# UHF_RFID_Nano_Shield.net
KiCad netlist of a schematic drawn in EAGLE
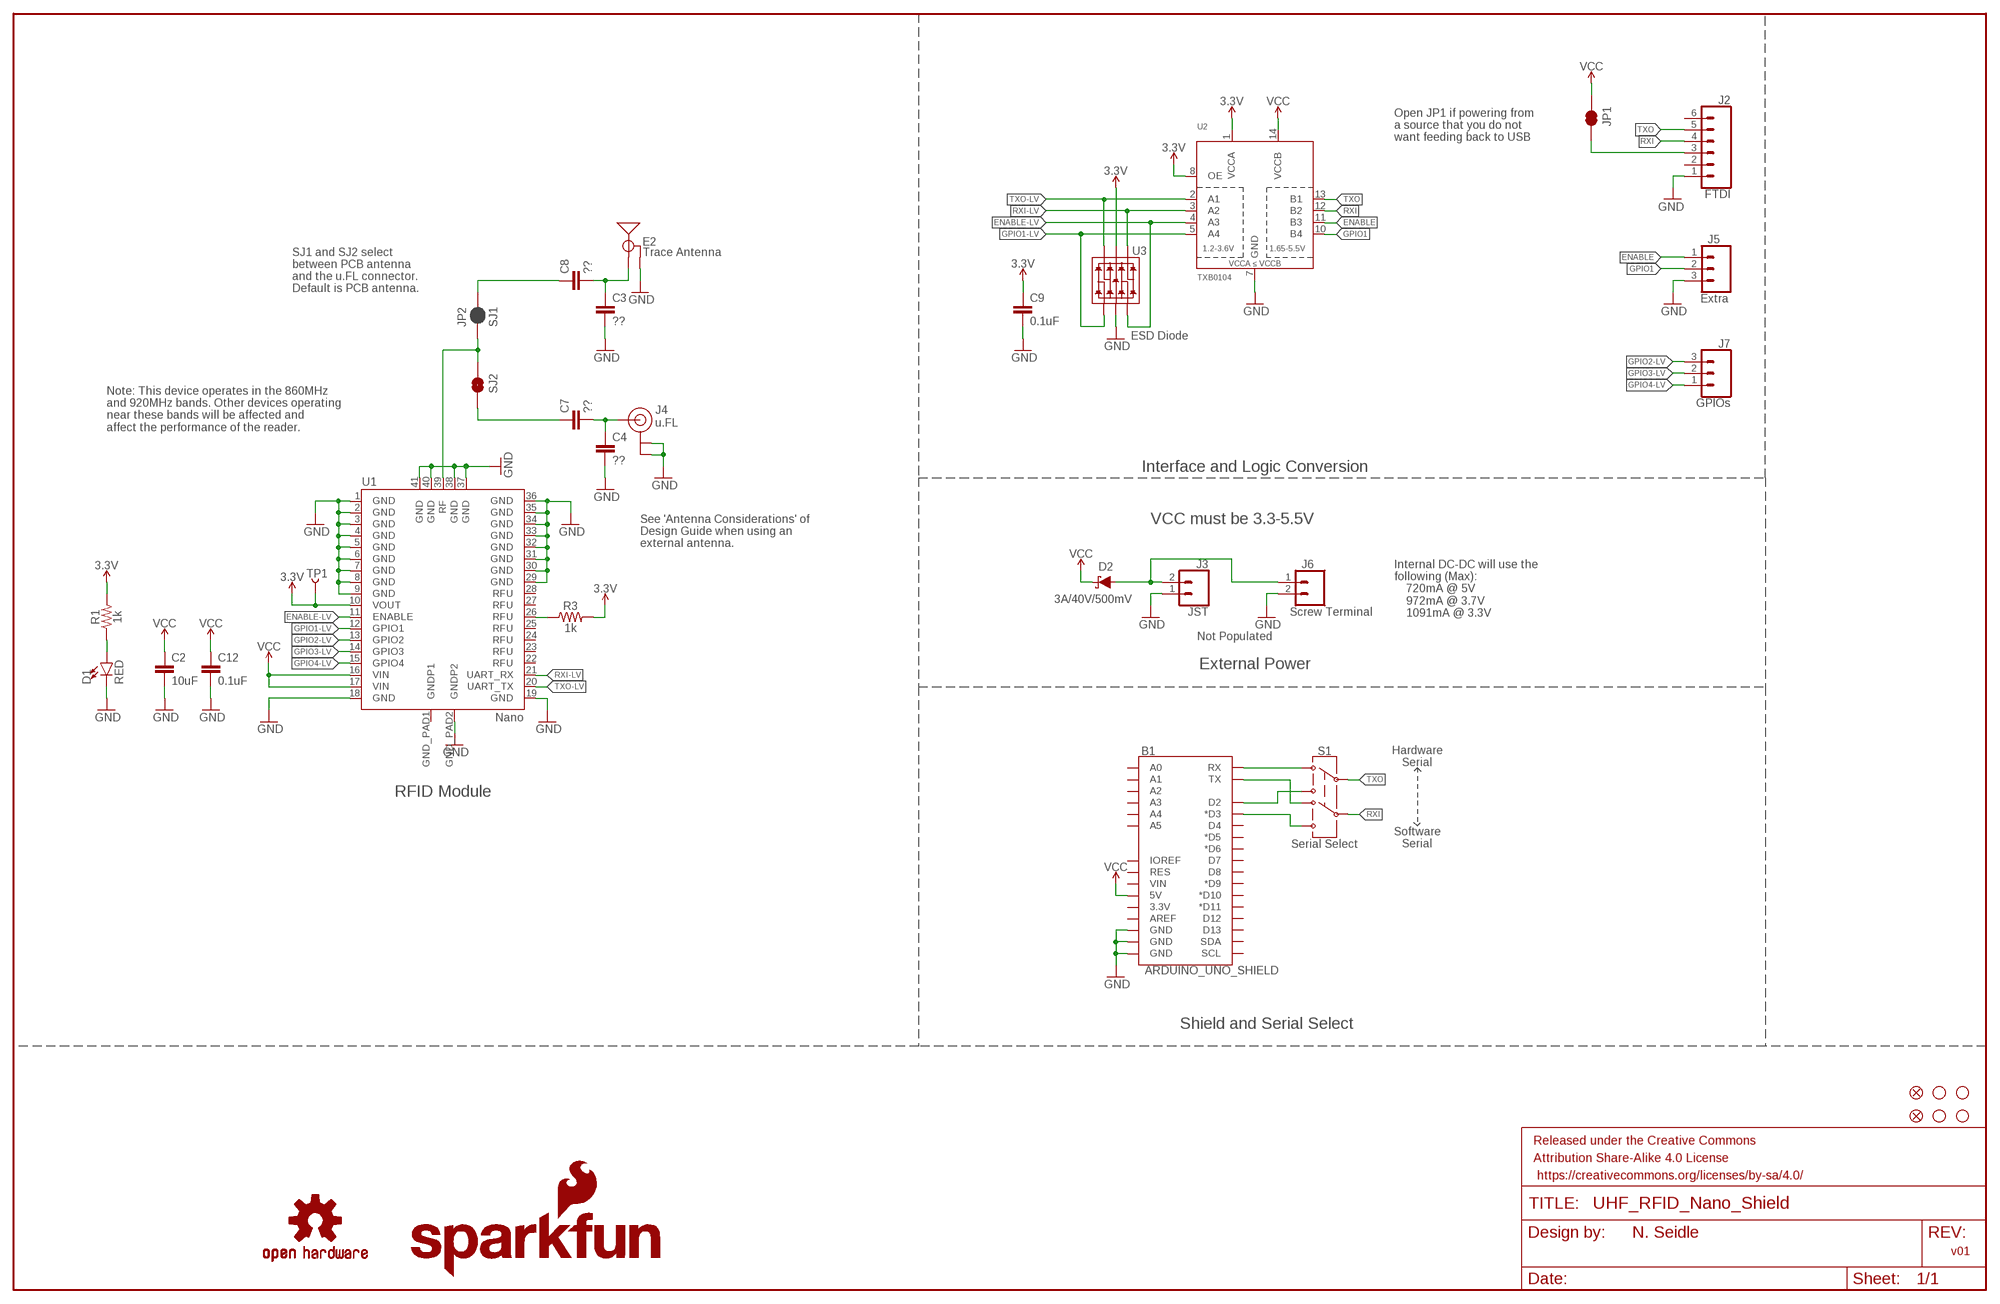
[diagram p0: schematic, sheet 1]

(export (version "E")
  (design (tool "Eeschema 10.0.6"))
  (components
    (comp (ref "B1")
      (value "ARDUINO_UNO_SHIELD")
      (footprint "eagle-import:UNO_R3_SHIELD")
      (libsource (lib "eagle-import") (part "ARDUINO_UNO_R3_SHIELDBASIC"))
    )
    (comp (ref "C2")
      (value "10uF")
      (footprint "eagle-import:0805")
      (libsource (lib "eagle-import") (part "10UF-0805-10V-10%"))
    )
    (comp (ref "C3")
      (value "??")
      (footprint "eagle-import:0603")
      (libsource (lib "eagle-import") (part "1.0PF-0603-50V-25%"))
    )
    (comp (ref "C4")
      (value "??")
      (footprint "eagle-import:0603")
      (libsource (lib "eagle-import") (part "1.0PF-0603-50V-25%"))
    )
    (comp (ref "C7")
      (value "??")
      (footprint "eagle-import:0603")
      (libsource (lib "eagle-import") (part "1.0PF-0603-50V-25%"))
    )
    (comp (ref "C8")
      (value "??")
      (footprint "eagle-import:0603")
      (libsource (lib "eagle-import") (part "1.0PF-0603-50V-25%"))
    )
    (comp (ref "C9")
      (value "0.1uF")
      (footprint "eagle-import:0603")
      (libsource (lib "eagle-import") (part "0.1UF-0603-25V-(+80/-20%)"))
    )
    (comp (ref "C12")
      (value "0.1uF")
      (footprint "eagle-import:0603")
      (libsource (lib "eagle-import") (part "0.1UF-0603-25V-(+80/-20%)"))
    )
    (comp (ref "D1")
      (value "RED")
      (footprint "eagle-import:LED-0603")
      (libsource (lib "eagle-import") (part "LED-RED0603"))
    )
    (comp (ref "D2")
      (value "3A/40V/500mV")
      (footprint "eagle-import:SMA-DIODE")
      (libsource (lib "eagle-import") (part "DIODE-SCHOTTKY-B340A"))
    )
    (comp (ref "E2")
      (value "Trace Antenna")
      (footprint "eagle-import:915MHZ_ANTENNA_TRIMBLE")
      (libsource (lib "eagle-import") (part "ANTENNA_GROUNDED1"))
    )
    (comp (ref "FID1")
      (value "FIDUCIAL1X2")
      (footprint "eagle-import:FIDUCIAL-1X2")
      (libsource (lib "eagle-import") (part "FIDUCIAL1X2"))
    )
    (comp (ref "FID2")
      (value "FIDUCIAL1X2")
      (footprint "eagle-import:FIDUCIAL-1X2")
      (libsource (lib "eagle-import") (part "FIDUCIAL1X2"))
    )
    (comp (ref "FRAME1")
      (value "FRAME-LEDGER")
      (footprint "eagle-import:CREATIVE_COMMONS")
      (libsource (lib "eagle-import") (part "FRAME-LEDGER"))
    )
    (comp (ref "J2")
      (value "FTDI")
      (footprint "eagle-import:1X06")
      (libsource (lib "eagle-import") (part "CONN_06SILK_FEMALE_PTH"))
    )
    (comp (ref "J3")
      (value "JST")
      (footprint "eagle-import:JST-2-PTH")
      (libsource (lib "eagle-import") (part "CONN_02JST-PTH-2"))
    )
    (comp (ref "J4")
      (value "U.FL")
      (footprint "eagle-import:U.FL")
      (libsource (lib "eagle-import") (part "U.FL"))
    )
    (comp (ref "J5")
      (value "Extra")
      (footprint "eagle-import:1X03")
      (libsource (lib "eagle-import") (part "CONN_03"))
    )
    (comp (ref "J6")
      (value "Screw Terminal")
      (footprint "eagle-import:SCREWTERMINAL-3.5MM-2")
      (libsource (lib "eagle-import") (part "CONN_023.5MM"))
    )
    (comp (ref "J7")
      (value "GPIOs")
      (footprint "eagle-import:1X03")
      (libsource (lib "eagle-import") (part "CONN_03"))
    )
    (comp (ref "JP1")
      (value "JUMPER-SMT_2_NC_TRACE_SILK")
      (footprint "eagle-import:SMT-JUMPER_2_NC_TRACE_SILK")
      (libsource (lib "eagle-import") (part "JUMPER-SMT_2_NC_TRACE_SILK"))
    )
    (comp (ref "JP2")
      (value "SJ1")
      (footprint "eagle-import:SMT-JUMPER_2_NO_NO-SILK")
      (libsource (lib "eagle-import") (part "JUMPER-SMT_2_NO_NO-SILK"))
    )
    (comp (ref "LOGO1")
      (value "SFE_LOGO_NAME_FLAME.1_INCH")
      (footprint "eagle-import:SFE_LOGO_NAME_FLAME_.1")
      (libsource (lib "eagle-import") (part "SFE_LOGO_NAME_FLAME.1_INCH"))
    )
    (comp (ref "LOGO2")
      (value "OSHW-LOGOS")
      (footprint "eagle-import:OSHW-LOGO-S")
      (libsource (lib "eagle-import") (part "OSHW-LOGOS"))
    )
    (comp (ref "LOGO3")
      (value "SFE_LOGO_NAME_FLAME.1_INCH")
      (footprint "eagle-import:SFE_LOGO_NAME_FLAME_.1")
      (libsource (lib "eagle-import") (part "SFE_LOGO_NAME_FLAME.1_INCH"))
    )
    (comp (ref "R1")
      (value "1k")
      (footprint "eagle-import:0603")
      (libsource (lib "eagle-import") (part "1KOHM-0603-1/10W-1%"))
    )
    (comp (ref "R3")
      (value "1k")
      (footprint "eagle-import:0603")
      (libsource (lib "eagle-import") (part "1KOHM-0603-1/10W-1%"))
    )
    (comp (ref "S1")
      (value "Serial Select")
      (footprint "eagle-import:SWITCH_DPDT_SMD_AYZ0202")
      (libsource (lib "eagle-import") (part "SWITCH-DPDT-SMD-AYZ0202"))
    )
    (comp (ref "SJ2")
      (value "JUMPER-SMT_2_NO_NO-SILK")
      (footprint "eagle-import:SMT-JUMPER_2_NO_NO-SILK")
      (libsource (lib "eagle-import") (part "JUMPER-SMT_2_NO_NO-SILK"))
    )
    (comp (ref "STANDOFF1")
      (value "STAND-OFF")
      (footprint "eagle-import:STAND-OFF")
      (libsource (lib "eagle-import") (part "STAND-OFF"))
    )
    (comp (ref "STANDOFF2")
      (value "STAND-OFF")
      (footprint "eagle-import:STAND-OFF")
      (libsource (lib "eagle-import") (part "STAND-OFF"))
    )
    (comp (ref "STANDOFF3")
      (value "STAND-OFF")
      (footprint "eagle-import:STAND-OFF")
      (libsource (lib "eagle-import") (part "STAND-OFF"))
    )
    (comp (ref "STANDOFF4")
      (value "STAND-OFF")
      (footprint "eagle-import:STAND-OFF")
      (libsource (lib "eagle-import") (part "STAND-OFF"))
    )
    (comp (ref "TP1")
      (value "TEST-POINT3")
      (footprint "eagle-import:PAD.03X.03")
      (libsource (lib "eagle-import") (part "TEST-POINT3"))
    )
    (comp (ref "U1")
      (value "Nano")
      (footprint "eagle-import:NANO_MODULE")
      (libsource (lib "eagle-import") (part "UHF_RFID_NANO_MODULE"))
    )
    (comp (ref "U2")
      (value "TXB0104")
      (footprint "eagle-import:SO14")
      (libsource (lib "eagle-import") (part "TXB0104PWRSOIC14"))
    )
    (comp (ref "U3")
      (value "ESD Diode")
      (footprint "eagle-import:SOT-23-6")
      (libsource (lib "eagle-import") (part "TVS_DIODE_ARRAYSMD"))
    )
  )
  (nets
    (net (code "1") (name "3.3V") (class "Default")
      (node (ref "C9") (pin "1") (pinfunction "1_1") (pintype "passive"))
      (node (ref "R1") (pin "2") (pinfunction "2_2") (pintype "passive"))
      (node (ref "R3") (pin "2") (pinfunction "2_2") (pintype "passive"))
      (node (ref "TP1") (pin "P$1") (pinfunction "1_P$1") (pintype "bidirectional"))
      (node (ref "U1") (pin "10") (pinfunction "VOUT_10") (pintype "bidirectional"))
      (node (ref "U2") (pin "1") (pinfunction "VCCA_1") (pintype "bidirectional"))
      (node (ref "U2") (pin "8") (pinfunction "OE_8") (pintype "bidirectional"))
      (node (ref "U3") (pin "5") (pinfunction "VCC_5") (pintype "bidirectional"))
    )
    (net (code "2") (name "ENABLE") (class "Default")
      (node (ref "J5") (pin "1") (pinfunction "1_1") (pintype "passive"))
      (node (ref "U2") (pin "11") (pinfunction "B3_11") (pintype "bidirectional"))
    )
    (net (code "3") (name "ENABLE-LV") (class "Default")
      (node (ref "U1") (pin "11") (pinfunction "ENABLE_11") (pintype "bidirectional"))
      (node (ref "U2") (pin "4") (pinfunction "A3_4") (pintype "bidirectional"))
      (node (ref "U3") (pin "3") (pinfunction "IO2_3") (pintype "bidirectional"))
    )
    (net (code "4") (name "GND") (class "Default")
      (node (ref "B1") (pin "GND@0") (pinfunction "GND_GND@0") (pintype "bidirectional"))
      (node (ref "B1") (pin "GND@1") (pinfunction "GND_GND@1") (pintype "bidirectional"))
      (node (ref "B1") (pin "GND@2") (pinfunction "GND_GND@2") (pintype "bidirectional"))
      (node (ref "C12") (pin "2") (pinfunction "2_2") (pintype "passive"))
      (node (ref "C2") (pin "2") (pinfunction "2_2") (pintype "passive"))
      (node (ref "C3") (pin "2") (pinfunction "2_2") (pintype "passive"))
      (node (ref "C4") (pin "2") (pinfunction "2_2") (pintype "passive"))
      (node (ref "C9") (pin "2") (pinfunction "2_2") (pintype "passive"))
      (node (ref "D1") (pin "C") (pinfunction "C_C") (pintype "passive"))
      (node (ref "E2") (pin "GND@1") (pinfunction "GND_GND@1") (pintype "bidirectional"))
      (node (ref "E2") (pin "GND@2") (pinfunction "GND_GND@2") (pintype "bidirectional"))
      (node (ref "E2") (pin "GND@3") (pinfunction "GND_GND@3") (pintype "bidirectional"))
      (node (ref "J2") (pin "1") (pinfunction "1_1") (pintype "passive"))
      (node (ref "J3") (pin "1") (pinfunction "1_1") (pintype "passive"))
      (node (ref "J4") (pin "P$1") (pinfunction "GND_P$1") (pintype "bidirectional"))
      (node (ref "J4") (pin "P$2") (pinfunction "GND_P$2") (pintype "bidirectional"))
      (node (ref "J5") (pin "3") (pinfunction "3_3") (pintype "passive"))
      (node (ref "J6") (pin "2") (pinfunction "2_2") (pintype "passive"))
      (node (ref "U1") (pin "1") (pinfunction "GND_1") (pintype "bidirectional"))
      (node (ref "U1") (pin "18") (pinfunction "GND_18") (pintype "bidirectional"))
      (node (ref "U1") (pin "19") (pinfunction "GND_19") (pintype "bidirectional"))
      (node (ref "U1") (pin "2") (pinfunction "GND_2") (pintype "bidirectional"))
      (node (ref "U1") (pin "29") (pinfunction "GND_29") (pintype "bidirectional"))
      (node (ref "U1") (pin "3") (pinfunction "GND_3") (pintype "bidirectional"))
      (node (ref "U1") (pin "30") (pinfunction "GND_30") (pintype "bidirectional"))
      (node (ref "U1") (pin "31") (pinfunction "GND_31") (pintype "bidirectional"))
      (node (ref "U1") (pin "32") (pinfunction "GND_32") (pintype "bidirectional"))
      (node (ref "U1") (pin "33") (pinfunction "GND_33") (pintype "bidirectional"))
      (node (ref "U1") (pin "34") (pinfunction "GND_34") (pintype "bidirectional"))
      (node (ref "U1") (pin "35") (pinfunction "GND_35") (pintype "bidirectional"))
      (node (ref "U1") (pin "36") (pinfunction "GND_36") (pintype "bidirectional"))
      (node (ref "U1") (pin "37") (pinfunction "GND_37") (pintype "bidirectional"))
      (node (ref "U1") (pin "38") (pinfunction "GND_38") (pintype "bidirectional"))
      (node (ref "U1") (pin "4") (pinfunction "GND_4") (pintype "bidirectional"))
      (node (ref "U1") (pin "40") (pinfunction "GND_40") (pintype "bidirectional"))
      (node (ref "U1") (pin "41") (pinfunction "GND_41") (pintype "bidirectional"))
      (node (ref "U1") (pin "5") (pinfunction "GND_5") (pintype "bidirectional"))
      (node (ref "U1") (pin "6") (pinfunction "GND_6") (pintype "bidirectional"))
      (node (ref "U1") (pin "7") (pinfunction "GND_7") (pintype "bidirectional"))
      (node (ref "U1") (pin "8") (pinfunction "GND_8") (pintype "bidirectional"))
      (node (ref "U1") (pin "9") (pinfunction "GND_9") (pintype "bidirectional"))
      (node (ref "U1") (pin "GND_PAD2") (pinfunction "GNDP2_GND_PAD2") (pintype "bidirectional"))
      (node (ref "U2") (pin "7") (pinfunction "GND_7") (pintype "bidirectional"))
      (node (ref "U3") (pin "2") (pinfunction "VSS_2") (pintype "bidirectional"))
    )
    (net (code "5") (name "GPIO1") (class "Default")
      (node (ref "J5") (pin "2") (pinfunction "2_2") (pintype "passive"))
      (node (ref "U2") (pin "10") (pinfunction "B4_10") (pintype "bidirectional"))
    )
    (net (code "6") (name "GPIO1-LV") (class "Default")
      (node (ref "U1") (pin "12") (pinfunction "GPIO1_12") (pintype "bidirectional"))
      (node (ref "U2") (pin "5") (pinfunction "A4_5") (pintype "bidirectional"))
      (node (ref "U3") (pin "1") (pinfunction "IO1_1") (pintype "bidirectional"))
    )
    (net (code "7") (name "GPIO2-LV") (class "Default")
      (node (ref "J7") (pin "3") (pinfunction "3_3") (pintype "passive"))
      (node (ref "U1") (pin "13") (pinfunction "GPIO2_13") (pintype "bidirectional"))
    )
    (net (code "8") (name "GPIO3-LV") (class "Default")
      (node (ref "J7") (pin "2") (pinfunction "2_2") (pintype "passive"))
      (node (ref "U1") (pin "14") (pinfunction "GPIO3_14") (pintype "bidirectional"))
    )
    (net (code "9") (name "GPIO4-LV") (class "Default")
      (node (ref "J7") (pin "1") (pinfunction "1_1") (pintype "passive"))
      (node (ref "U1") (pin "15") (pinfunction "GPIO4_15") (pintype "bidirectional"))
    )
    (net (code "10") (name "Net-(B1-*D3)") (class "Default")
      (node (ref "B1") (pin "D3") (pinfunction "*D3_D3") (pintype "bidirectional"))
      (node (ref "S1") (pin "6") (pinfunction "6_6") (pintype "bidirectional"))
    )
    (net (code "11") (name "Net-(B1-PadD2)") (class "Default")
      (node (ref "B1") (pin "D2") (pinfunction "D2_D2") (pintype "bidirectional"))
      (node (ref "S1") (pin "3") (pinfunction "3_3") (pintype "bidirectional"))
    )
    (net (code "12") (name "Net-(B1-PadRX)") (class "Default")
      (node (ref "B1") (pin "RX") (pinfunction "RX_RX") (pintype "bidirectional"))
      (node (ref "S1") (pin "1") (pinfunction "1_1") (pintype "bidirectional"))
    )
    (net (code "13") (name "Net-(B1-PadTX)") (class "Default")
      (node (ref "B1") (pin "TX") (pinfunction "TX_TX") (pintype "bidirectional"))
      (node (ref "S1") (pin "4") (pinfunction "4_4") (pintype "bidirectional"))
    )
    (net (code "14") (name "Net-(C7-Pad1)") (class "Default")
      (node (ref "C7") (pin "1") (pinfunction "1_1") (pintype "passive"))
      (node (ref "SJ2") (pin "2") (pinfunction "2_2") (pintype "passive"))
    )
    (net (code "15") (name "Net-(C8-Pad1)") (class "Default")
      (node (ref "C8") (pin "1") (pinfunction "1_1") (pintype "passive"))
      (node (ref "JP2") (pin "2") (pinfunction "2_2") (pintype "passive"))
    )
    (net (code "16") (name "Net-(D1-PadA)") (class "Default")
      (node (ref "D1") (pin "A") (pinfunction "A_A") (pintype "passive"))
      (node (ref "R1") (pin "1") (pinfunction "1_1") (pintype "passive"))
    )
    (net (code "17") (name "Net-(D2-PadA)") (class "Default")
      (node (ref "D2") (pin "A") (pinfunction "A_A") (pintype "passive"))
      (node (ref "J3") (pin "2") (pinfunction "2_2") (pintype "passive"))
      (node (ref "J6") (pin "1") (pinfunction "1_1") (pintype "passive"))
    )
    (net (code "18") (name "Net-(E2-SIGNAL)") (class "Default")
      (node (ref "C3") (pin "1") (pinfunction "1_1") (pintype "passive"))
      (node (ref "C8") (pin "2") (pinfunction "2_2") (pintype "passive"))
      (node (ref "E2") (pin "ANT") (pinfunction "SIGNAL_ANT") (pintype "bidirectional"))
    )
    (net (code "19") (name "Net-(J2-Pad3)") (class "Default")
      (node (ref "J2") (pin "3") (pinfunction "3_3") (pintype "passive"))
      (node (ref "JP1") (pin "2") (pinfunction "2_2") (pintype "passive"))
    )
    (net (code "20") (name "Net-(J4-SIGNAL)") (class "Default")
      (node (ref "C4") (pin "1") (pinfunction "1_1") (pintype "passive"))
      (node (ref "C7") (pin "2") (pinfunction "2_2") (pintype "passive"))
      (node (ref "J4") (pin "P$3") (pinfunction "SIGNAL_P$3") (pintype "bidirectional"))
    )
    (net (code "21") (name "Net-(R3-Pad1)") (class "Default")
      (node (ref "R3") (pin "1") (pinfunction "1_1") (pintype "passive"))
      (node (ref "U1") (pin "26") (pinfunction "RFU_26") (pintype "bidirectional"))
    )
    (net (code "22") (name "Net-(U1-RF)") (class "Default")
      (node (ref "JP2") (pin "1") (pinfunction "1_1") (pintype "passive"))
      (node (ref "SJ2") (pin "1") (pinfunction "1_1") (pintype "passive"))
      (node (ref "U1") (pin "39") (pinfunction "RF_39") (pintype "bidirectional"))
    )
    (net (code "23") (name "RXI") (class "Default")
      (node (ref "J2") (pin "4") (pinfunction "4_4") (pintype "passive"))
      (node (ref "S1") (pin "5") (pinfunction "5_5") (pintype "bidirectional"))
      (node (ref "U2") (pin "12") (pinfunction "B2_12") (pintype "bidirectional"))
    )
    (net (code "24") (name "RXI-LV") (class "Default")
      (node (ref "U1") (pin "21") (pinfunction "UART_RX_21") (pintype "bidirectional"))
      (node (ref "U2") (pin "3") (pinfunction "A2_3") (pintype "bidirectional"))
      (node (ref "U3") (pin "4") (pinfunction "IO3_4") (pintype "bidirectional"))
    )
    (net (code "25") (name "TXO") (class "Default")
      (node (ref "J2") (pin "5") (pinfunction "5_5") (pintype "passive"))
      (node (ref "S1") (pin "2") (pinfunction "2_2") (pintype "bidirectional"))
      (node (ref "U2") (pin "13") (pinfunction "B1_13") (pintype "bidirectional"))
    )
    (net (code "26") (name "TXO-LV") (class "Default")
      (node (ref "U1") (pin "20") (pinfunction "UART_TX_20") (pintype "bidirectional"))
      (node (ref "U2") (pin "2") (pinfunction "A1_2") (pintype "bidirectional"))
      (node (ref "U3") (pin "6") (pinfunction "IO4_6") (pintype "bidirectional"))
    )
    (net (code "27") (name "VCC") (class "Default")
      (node (ref "B1") (pin "5V") (pinfunction "5V_5V") (pintype "bidirectional"))
      (node (ref "C12") (pin "1") (pinfunction "1_1") (pintype "passive"))
      (node (ref "C2") (pin "1") (pinfunction "1_1") (pintype "passive"))
      (node (ref "D2") (pin "C") (pinfunction "C_C") (pintype "passive"))
      (node (ref "JP1") (pin "1") (pinfunction "1_1") (pintype "passive"))
      (node (ref "U1") (pin "16") (pinfunction "VIN_16") (pintype "bidirectional"))
      (node (ref "U1") (pin "17") (pinfunction "VIN_17") (pintype "bidirectional"))
      (node (ref "U2") (pin "14") (pinfunction "VCCB_14") (pintype "bidirectional"))
    )
    (net (code "28") (name "unconnected-(B1-*D5-PadD5)") (class "Default")
      (node (ref "B1") (pin "D5") (pinfunction "*D5_D5") (pintype "bidirectional"))
    )
    (net (code "29") (name "unconnected-(B1-*D6-PadD6)") (class "Default")
      (node (ref "B1") (pin "D6") (pinfunction "*D6_D6") (pintype "bidirectional"))
    )
    (net (code "30") (name "unconnected-(B1-*D9-PadD9)") (class "Default")
      (node (ref "B1") (pin "D9") (pinfunction "*D9_D9") (pintype "bidirectional"))
    )
    (net (code "31") (name "unconnected-(B1-*D10-PadD10)") (class "Default")
      (node (ref "B1") (pin "D10") (pinfunction "*D10_D10") (pintype "bidirectional"))
    )
    (net (code "32") (name "unconnected-(B1-*D11-PadD11)") (class "Default")
      (node (ref "B1") (pin "D11") (pinfunction "*D11_D11") (pintype "bidirectional"))
    )
    (net (code "33") (name "unconnected-(B1-Pad3.3V)") (class "Default")
      (node (ref "B1") (pin "3.3V") (pinfunction "3.3V_3.3V") (pintype "bidirectional"))
    )
    (net (code "34") (name "unconnected-(B1-PadA0)") (class "Default")
      (node (ref "B1") (pin "A0") (pinfunction "A0_A0") (pintype "bidirectional"))
    )
    (net (code "35") (name "unconnected-(B1-PadA1)") (class "Default")
      (node (ref "B1") (pin "A1") (pinfunction "A1_A1") (pintype "bidirectional"))
    )
    (net (code "36") (name "unconnected-(B1-PadA2)") (class "Default")
      (node (ref "B1") (pin "A2") (pinfunction "A2_A2") (pintype "bidirectional"))
    )
    (net (code "37") (name "unconnected-(B1-PadA3)") (class "Default")
      (node (ref "B1") (pin "A3") (pinfunction "A3_A3") (pintype "bidirectional"))
    )
    (net (code "38") (name "unconnected-(B1-PadA4)") (class "Default")
      (node (ref "B1") (pin "A4") (pinfunction "A4_A4") (pintype "bidirectional"))
    )
    (net (code "39") (name "unconnected-(B1-PadA5)") (class "Default")
      (node (ref "B1") (pin "A5") (pinfunction "A5_A5") (pintype "bidirectional"))
    )
    (net (code "40") (name "unconnected-(B1-PadAREF)") (class "Default")
      (node (ref "B1") (pin "AREF") (pinfunction "AREF_AREF") (pintype "bidirectional"))
    )
    (net (code "41") (name "unconnected-(B1-PadD4)") (class "Default")
      (node (ref "B1") (pin "D4") (pinfunction "D4_D4") (pintype "bidirectional"))
    )
    (net (code "42") (name "unconnected-(B1-PadD7)") (class "Default")
      (node (ref "B1") (pin "D7") (pinfunction "D7_D7") (pintype "bidirectional"))
    )
    (net (code "43") (name "unconnected-(B1-PadD8)") (class "Default")
      (node (ref "B1") (pin "D8") (pinfunction "D8_D8") (pintype "bidirectional"))
    )
    (net (code "44") (name "unconnected-(B1-PadD12)") (class "Default")
      (node (ref "B1") (pin "D12") (pinfunction "D12_D12") (pintype "bidirectional"))
    )
    (net (code "45") (name "unconnected-(B1-PadD13)") (class "Default")
      (node (ref "B1") (pin "D13") (pinfunction "D13_D13") (pintype "bidirectional"))
    )
    (net (code "46") (name "unconnected-(B1-PadIOREF)") (class "Default")
      (node (ref "B1") (pin "IOREF") (pinfunction "IOREF_IOREF") (pintype "bidirectional"))
    )
    (net (code "47") (name "unconnected-(B1-PadRES)") (class "Default")
      (node (ref "B1") (pin "RES") (pinfunction "RES_RES") (pintype "bidirectional"))
    )
    (net (code "48") (name "unconnected-(B1-PadSCL)") (class "Default")
      (node (ref "B1") (pin "SCL") (pinfunction "SCL_SCL") (pintype "bidirectional"))
    )
    (net (code "49") (name "unconnected-(B1-PadSDA)") (class "Default")
      (node (ref "B1") (pin "SDA") (pinfunction "SDA_SDA") (pintype "bidirectional"))
    )
    (net (code "50") (name "unconnected-(B1-PadVIN)") (class "Default")
      (node (ref "B1") (pin "VIN") (pinfunction "VIN_VIN") (pintype "bidirectional"))
    )
    (net (code "51") (name "unconnected-(J2-Pad2)") (class "Default")
      (node (ref "J2") (pin "2") (pinfunction "2_2") (pintype "passive"))
    )
    (net (code "52") (name "unconnected-(J2-Pad6)") (class "Default")
      (node (ref "J2") (pin "6") (pinfunction "6_6") (pintype "passive"))
    )
    (net (code "53") (name "unconnected-(U1-GNDP1-PadGND_PAD1)") (class "Default")
      (node (ref "U1") (pin "GND_PAD1") (pinfunction "GNDP1_GND_PAD1") (pintype "bidirectional"))
    )
    (net (code "54") (name "unconnected-(U1-RFU-Pad22)") (class "Default")
      (node (ref "U1") (pin "22") (pinfunction "RFU_22") (pintype "bidirectional"))
    )
    (net (code "55") (name "unconnected-(U1-RFU-Pad23)") (class "Default")
      (node (ref "U1") (pin "23") (pinfunction "RFU_23") (pintype "bidirectional"))
    )
    (net (code "56") (name "unconnected-(U1-RFU-Pad24)") (class "Default")
      (node (ref "U1") (pin "24") (pinfunction "RFU_24") (pintype "bidirectional"))
    )
    (net (code "57") (name "unconnected-(U1-RFU-Pad25)") (class "Default")
      (node (ref "U1") (pin "25") (pinfunction "RFU_25") (pintype "bidirectional"))
    )
    (net (code "58") (name "unconnected-(U1-RFU-Pad27)") (class "Default")
      (node (ref "U1") (pin "27") (pinfunction "RFU_27") (pintype "bidirectional"))
    )
    (net (code "59") (name "unconnected-(U1-RFU-Pad28)") (class "Default")
      (node (ref "U1") (pin "28") (pinfunction "RFU_28") (pintype "bidirectional"))
    )
  )
)
